# ChargerDeviceSchematic.net
KiCad netlist of a schematic drawn in Altium Designer
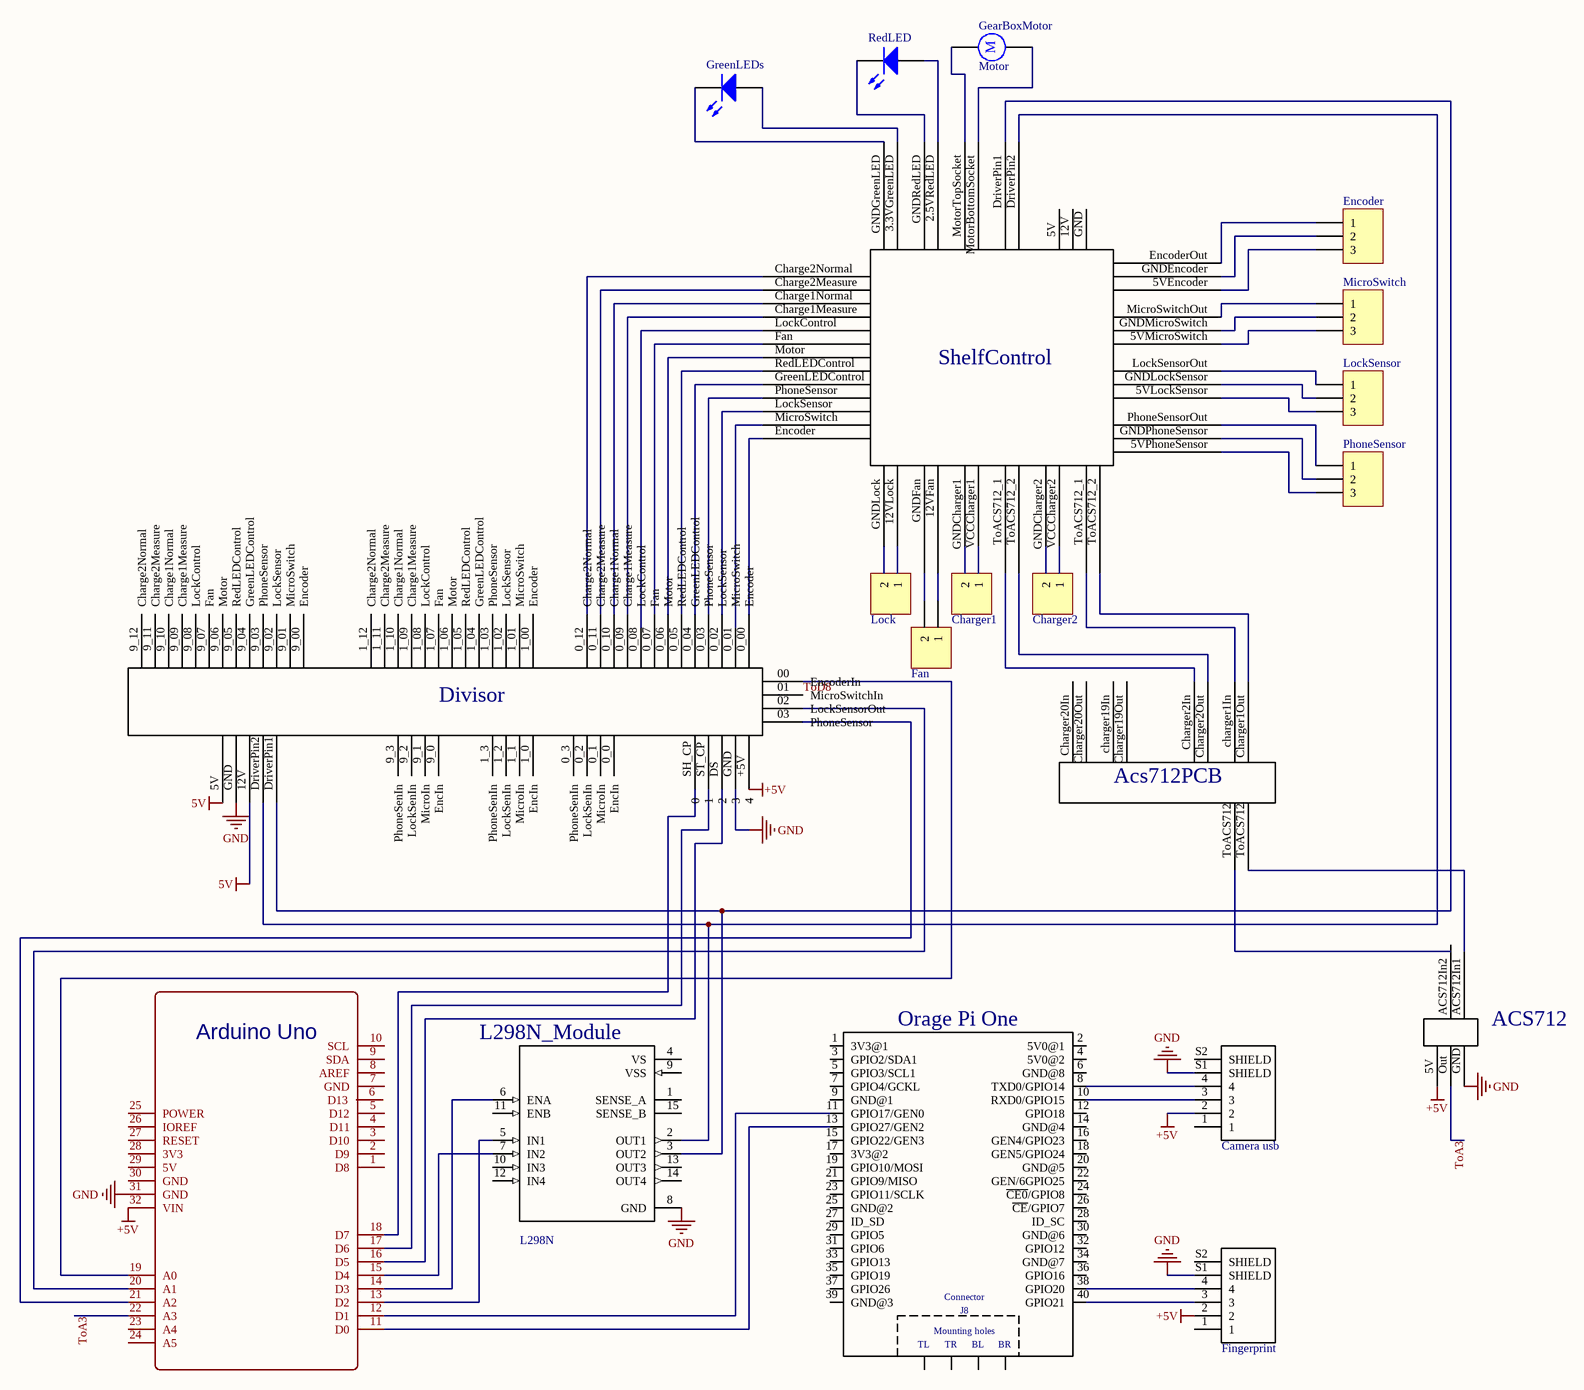
[diagram p0: ChargerDeviceSchematic.SchDoc]

(export (version "E")
  (design (tool "Eeschema 10.0.6"))
  (components
    (comp (ref "ACS712")
      (value "~")
      (footprint "CBB22")
      (description "Polypropylene film with epoxy Cap CBB22 105J400V")
      (fields (field (name "MANUFACTURER") "CHINA") (field (name "DESIGNER") "Abbas Basereh"))
      (libsource (lib "acs712") (part "Component_1"))
    )
    (comp (ref "Acs712PCB")
      (value "~")
      (footprint "CBB22")
      (description "Polypropylene film with epoxy Cap CBB22 105J400V")
      (fields (field (name "MANUFACTURER") "CHINA") (field (name "DESIGNER") "Abbas Basereh"))
      (libsource (lib "ACS712-connectBoard") (part "Component_1"))
    )
    (comp (ref "Arduino Uno")
      (value "~")
      (footprint "UNO_R3")
      (fields (field (name "BOM_MANUFACTURER PART") "?"))
      (libsource (lib "altium-import") (part "root_3_UNO_R3_"))
    )
    (comp (ref "Camera usb")
      (value "1-292303-1")
      (footprint "*TE_1-292303-1_1-292303-1(Primary)")
      (description "Conn USB 2.0 Type A RCP 4 POS Solder RA SMD 4 Terminal 1 Port Box/Tray")
      (fields (field (name "MF") "TE Connectivity"))
      (libsource (lib "1-292303-1") (part "1-292303-1"))
    )
    (comp (ref "Charger1")
      (value "~")
      (footprint "HDR1X2")
      (description "Header, 2-Pin")
      (fields (field (name "PUBLISHER") "Altium Limited"))
      (libsource (lib "Miscellaneous Connectors") (part "Header 2"))
    )
    (comp (ref "Charger2")
      (value "~")
      (footprint "HDR1X2")
      (description "Header, 2-Pin")
      (fields (field (name "PUBLISHER") "Altium Limited"))
      (libsource (lib "Miscellaneous Connectors") (part "Header 2"))
    )
    (comp (ref "Divisor")
      (value "~")
      (footprint "CBB22")
      (description "Polypropylene film with epoxy Cap CBB22 105J400V")
      (fields (field (name "MANUFACTURER") "CHINA") (field (name "DESIGNER") "Abbas Basereh"))
      (libsource (lib "divisor") (part "Component_1"))
    )
    (comp (ref "Encoder")
      (value "~")
      (footprint "HDR1X3")
      (description "Header, 3-Pin")
      (fields (field (name "PUBLISHER") "Altium Limited"))
      (libsource (lib "Miscellaneous Connectors") (part "Header 3"))
    )
    (comp (ref "Fan")
      (value "~")
      (footprint "HDR1X2")
      (description "Header, 2-Pin")
      (fields (field (name "PUBLISHER") "Altium Limited"))
      (libsource (lib "Miscellaneous Connectors") (part "Header 2"))
    )
    (comp (ref "Fingerprint")
      (value "1-292303-1")
      (footprint "*TE_1-292303-1_1-292303-1(Primary)")
      (description "Conn USB 2.0 Type A RCP 4 POS Solder RA SMD 4 Terminal 1 Port Box/Tray")
      (fields (field (name "MF") "TE Connectivity"))
      (libsource (lib "1-292303-1") (part "1-292303-1"))
    )
    (comp (ref "GearBoxMotor")
      (value "Motor")
      (footprint "RB5-10.5")
      (description "Motor, General Kind")
      (fields (field (name "PUBLISHER") "Altium Limited"))
      (libsource (lib "Miscellaneous Devices") (part "Motor"))
    )
    (comp (ref "GreenLEDs")
      (value "~")
      (footprint "3.2X1.6X1.1")
      (description "Typical RED, GREEN, YELLOW, AMBER GaAs LED")
      (fields (field (name "PUBLISHER") "Altium Limited"))
      (libsource (lib "Miscellaneous Devices") (part "LED2"))
    )
    (comp (ref "L298N_Module")
      (value "L298N")
      (footprint "*TO127P2020X500X2100-15")
      (description "Dual Full Bridge Motor Driver 15-Pin_15+Tab_ MULTIWATT V Tube")
      (fields (field (name "MF") "STMicroelectronics"))
      (libsource (lib "L298N") (part "L298N"))
    )
    (comp (ref "Lock")
      (value "~")
      (footprint "HDR1X2")
      (description "Header, 2-Pin")
      (fields (field (name "PUBLISHER") "Altium Limited"))
      (libsource (lib "Miscellaneous Connectors") (part "Header 2"))
    )
    (comp (ref "LockSensor")
      (value "~")
      (footprint "HDR1X3")
      (description "Header, 3-Pin")
      (fields (field (name "PUBLISHER") "Altium Limited"))
      (libsource (lib "Miscellaneous Connectors") (part "Header 3"))
    )
    (comp (ref "MicroSwitch")
      (value "~")
      (footprint "HDR1X3")
      (description "Header, 3-Pin")
      (fields (field (name "PUBLISHER") "Altium Limited"))
      (libsource (lib "Miscellaneous Connectors") (part "Header 3"))
    )
    (comp (ref "Orage Pi One")
      (value "~")
      (footprint "*RASPBERRY_PI_B+_RASPBERRY_PI_B+(Primary)")
      (description "Single Board Computer; 700Mhz; 512Mb RAM; 85.6x53.98x17mm; Raspberry Pi B+ Series")
      (fields (field (name "MF") "Raspberry Pi") (field (name "MP") "RASPBERRY PI B+"))
      (libsource (lib "RASPBERRY_PI_B_") (part "RASPBERRY_PI_B+"))
    )
    (comp (ref "PhoneSensor")
      (value "~")
      (footprint "HDR1X3")
      (description "Header, 3-Pin")
      (fields (field (name "PUBLISHER") "Altium Limited"))
      (libsource (lib "Miscellaneous Connectors") (part "Header 3"))
    )
    (comp (ref "RedLED")
      (value "~")
      (footprint "3.2X1.6X1.1")
      (description "Typical RED, GREEN, YELLOW, AMBER GaAs LED")
      (fields (field (name "PUBLISHER") "Altium Limited"))
      (libsource (lib "Miscellaneous Devices") (part "LED2"))
    )
    (comp (ref "ShelfControl")
      (value "~")
      (footprint "CBB22")
      (description "Polypropylene film with epoxy Cap CBB22 105J400V")
      (fields (field (name "MANUFACTURER") "CHINA") (field (name "DESIGNER") "Abbas Basereh"))
      (libsource (lib "shelfControl 5V") (part "Component_1"))
    )
  )
  (nets
    (net (code "1") (name "+5V") (class "Default")
      (node (ref "Arduino Uno") (pin "32") (pinfunction "VIN_32") (pintype "passive"))
      (node (ref "Camera usb") (pin "2") (pinfunction "2_2") (pintype "passive"))
      (node (ref "Fingerprint") (pin "2") (pinfunction "2_2") (pintype "passive"))
    )
    (net (code "2") (name "/ToA3") (class "Default")
      (node (ref "Arduino Uno") (pin "22") (pinfunction "A3_22") (pintype "passive"))
    )
    (net (code "5") (name "GND") (class "Default")
      (node (ref "Arduino Uno") (pin "31") (pinfunction "GND_31") (pintype "passive"))
      (node (ref "Camera usb") (pin "S1") (pinfunction "SHIELD_S1") (pintype "passive"))
      (node (ref "Fingerprint") (pin "S1") (pinfunction "SHIELD_S1") (pintype "passive"))
      (node (ref "L298N_Module") (pin "8") (pinfunction "GND_8") (pintype "power_in"))
    )
    (net (code "6") (name "Net-(Arduino Uno-D0)") (class "Default")
      (node (ref "Arduino Uno") (pin "11") (pinfunction "D0_11") (pintype "passive"))
      (node (ref "Orage Pi One") (pin "13") (pinfunction "GPIO27/GEN2_13") (pintype "bidirectional"))
    )
    (net (code "7") (name "Net-(Arduino Uno-D1)") (class "Default")
      (node (ref "Arduino Uno") (pin "12") (pinfunction "D1_12") (pintype "passive"))
      (node (ref "Orage Pi One") (pin "11") (pinfunction "GPIO17/GEN0_11") (pintype "bidirectional"))
    )
    (net (code "8") (name "Net-(Arduino Uno-D2)") (class "Default")
      (node (ref "Arduino Uno") (pin "13") (pinfunction "D2_13") (pintype "passive"))
      (node (ref "L298N_Module") (pin "5") (pinfunction "IN1_5") (pintype "input"))
    )
    (net (code "9") (name "Net-(Arduino Uno-D3)") (class "Default")
      (node (ref "Arduino Uno") (pin "14") (pinfunction "D3_14") (pintype "passive"))
      (node (ref "L298N_Module") (pin "6") (pinfunction "ENA_6") (pintype "input"))
    )
    (net (code "10") (name "Net-(Arduino Uno-D4)") (class "Default")
      (node (ref "Arduino Uno") (pin "15") (pinfunction "D4_15") (pintype "passive"))
      (node (ref "L298N_Module") (pin "7") (pinfunction "IN2_7") (pintype "input"))
    )
    (net (code "11") (name "Net-(Charger1-Pad1)") (class "Default")
      (node (ref "Charger1") (pin "1") (pinfunction "1_1") (pintype "passive"))
      (node (ref "ShelfControl") (pin "VCCCharger1") (pintype "passive"))
    )
    (net (code "12") (name "Net-(Charger1-Pad2)") (class "Default")
      (node (ref "Charger1") (pin "2") (pinfunction "2_2") (pintype "passive"))
      (node (ref "ShelfControl") (pin "GNDCharger1") (pintype "passive"))
    )
    (net (code "13") (name "Net-(Charger2-Pad1)") (class "Default")
      (node (ref "Charger2") (pin "1") (pinfunction "1_1") (pintype "passive"))
      (node (ref "ShelfControl") (pin "VCCCharger2") (pintype "passive"))
    )
    (net (code "14") (name "Net-(Charger2-Pad2)") (class "Default")
      (node (ref "Charger2") (pin "2") (pinfunction "2_2") (pintype "passive"))
      (node (ref "ShelfControl") (pin "GNDCharger2") (pintype "passive"))
    )
    (net (code "15") (name "Net-(Fan-Pad1)") (class "Default")
      (node (ref "Fan") (pin "1") (pinfunction "1_1") (pintype "passive"))
      (node (ref "ShelfControl") (pin "12VFan") (pintype "passive"))
    )
    (net (code "16") (name "Net-(Fan-Pad2)") (class "Default")
      (node (ref "Fan") (pin "2") (pinfunction "2_2") (pintype "passive"))
      (node (ref "ShelfControl") (pin "GNDFan") (pintype "passive"))
    )
    (net (code "17") (name "Net-(Lock-Pad1)") (class "Default")
      (node (ref "Lock") (pin "1") (pinfunction "1_1") (pintype "passive"))
      (node (ref "ShelfControl") (pin "12VLock") (pintype "passive"))
    )
    (net (code "18") (name "Net-(Lock-Pad2)") (class "Default")
      (node (ref "Lock") (pin "2") (pinfunction "2_2") (pintype "passive"))
      (node (ref "ShelfControl") (pin "GNDLock") (pintype "passive"))
    )
    (net (code "19") (name "Net-(Orage Pi One-GPIO20)") (class "Default")
      (node (ref "Fingerprint") (pin "4") (pinfunction "4_4") (pintype "passive"))
      (node (ref "Orage Pi One") (pin "38") (pinfunction "GPIO20_38") (pintype "bidirectional"))
    )
    (net (code "20") (name "Net-(Orage Pi One-GPIO21)") (class "Default")
      (node (ref "Fingerprint") (pin "3") (pinfunction "3_3") (pintype "passive"))
      (node (ref "Orage Pi One") (pin "40") (pinfunction "GPIO21_40") (pintype "bidirectional"))
    )
    (net (code "21") (name "Net-(Orage Pi One-RXD0{slash}GPIO15)") (class "Default")
      (node (ref "Camera usb") (pin "3") (pinfunction "3_3") (pintype "passive"))
      (node (ref "Orage Pi One") (pin "10") (pinfunction "RXD0/GPIO15_10") (pintype "bidirectional"))
    )
    (net (code "22") (name "Net-(Orage Pi One-TXD0{slash}GPIO14)") (class "Default")
      (node (ref "Camera usb") (pin "4") (pinfunction "4_4") (pintype "passive"))
      (node (ref "Orage Pi One") (pin "8") (pinfunction "TXD0/GPIO14_8") (pintype "bidirectional"))
    )
    (net (code "23") (name "unconnected-(ACS712-Pad5V)") (class "Default")
      (node (ref "ACS712") (pin "5V") (pintype "passive"))
    )
    (net (code "24") (name "unconnected-(ACS712-PadACS712In1)") (class "Default")
      (node (ref "ACS712") (pin "ACS712In1") (pintype "passive"))
    )
    (net (code "25") (name "unconnected-(ACS712-PadACS712In2)") (class "Default")
      (node (ref "ACS712") (pin "ACS712In2") (pintype "passive"))
    )
    (net (code "26") (name "unconnected-(ACS712-PadGND)") (class "Default")
      (node (ref "ACS712") (pin "GND") (pintype "passive"))
    )
    (net (code "27") (name "unconnected-(ACS712-PadOut)") (class "Default")
      (node (ref "ACS712") (pin "Out") (pintype "passive"))
    )
    (net (code "28") (name "unconnected-(Acs712PCB-PadCharger1Out)") (class "Default")
      (node (ref "Acs712PCB") (pin "Charger1Out") (pintype "passive"))
    )
    (net (code "29") (name "unconnected-(Acs712PCB-PadCharger2In)") (class "Default")
      (node (ref "Acs712PCB") (pin "Charger2In") (pintype "passive"))
    )
    (net (code "30") (name "unconnected-(Acs712PCB-PadCharger2Out)") (class "Default")
      (node (ref "Acs712PCB") (pin "Charger2Out") (pintype "passive"))
    )
    (net (code "31") (name "unconnected-(Acs712PCB-PadCharger19Out)") (class "Default")
      (node (ref "Acs712PCB") (pin "Charger19Out") (pintype "passive"))
    )
    (net (code "32") (name "unconnected-(Acs712PCB-PadCharger20In)") (class "Default")
      (node (ref "Acs712PCB") (pin "Charger20In") (pintype "passive"))
    )
    (net (code "33") (name "unconnected-(Acs712PCB-PadCharger20Out)") (class "Default")
      (node (ref "Acs712PCB") (pin "Charger20Out") (pintype "passive"))
    )
    (net (code "34") (name "unconnected-(Acs712PCB-PadToACS712)") (class "Default")
      (node (ref "Acs712PCB") (pin "ToACS712") (pintype "passive"))
    )
    (net (code "35") (name "unconnected-(Acs712PCB-PadToACS712)_1") (class "Default")
      (node (ref "Acs712PCB") (pin "ToACS712") (pintype "passive"))
    )
    (net (code "36") (name "unconnected-(Acs712PCB-Padcharger1In)") (class "Default")
      (node (ref "Acs712PCB") (pin "charger1In") (pintype "passive"))
    )
    (net (code "37") (name "unconnected-(Acs712PCB-Padcharger19In)") (class "Default")
      (node (ref "Acs712PCB") (pin "charger19In") (pintype "passive"))
    )
    (net (code "38") (name "unconnected-(Arduino Uno-3V3-Pad28)") (class "Default")
      (node (ref "Arduino Uno") (pin "28") (pinfunction "3V3_28") (pintype "passive"))
    )
    (net (code "39") (name "unconnected-(Arduino Uno-5V-Pad29)") (class "Default")
      (node (ref "Arduino Uno") (pin "29") (pinfunction "5V_29") (pintype "passive"))
    )
    (net (code "40") (name "unconnected-(Arduino Uno-A0-Pad19)") (class "Default")
      (node (ref "Arduino Uno") (pin "19") (pinfunction "A0_19") (pintype "passive"))
    )
    (net (code "41") (name "unconnected-(Arduino Uno-A1-Pad20)") (class "Default")
      (node (ref "Arduino Uno") (pin "20") (pinfunction "A1_20") (pintype "passive"))
    )
    (net (code "42") (name "unconnected-(Arduino Uno-A2-Pad21)") (class "Default")
      (node (ref "Arduino Uno") (pin "21") (pinfunction "A2_21") (pintype "passive"))
    )
    (net (code "43") (name "unconnected-(Arduino Uno-A4-Pad23)") (class "Default")
      (node (ref "Arduino Uno") (pin "23") (pinfunction "A4_23") (pintype "passive"))
    )
    (net (code "44") (name "unconnected-(Arduino Uno-A5-Pad24)") (class "Default")
      (node (ref "Arduino Uno") (pin "24") (pinfunction "A5_24") (pintype "passive"))
    )
    (net (code "45") (name "unconnected-(Arduino Uno-AREF-Pad8)") (class "Default")
      (node (ref "Arduino Uno") (pin "8") (pinfunction "AREF_8") (pintype "passive"))
    )
    (net (code "46") (name "unconnected-(Arduino Uno-D5-Pad16)") (class "Default")
      (node (ref "Arduino Uno") (pin "16") (pinfunction "D5_16") (pintype "passive"))
    )
    (net (code "47") (name "unconnected-(Arduino Uno-D6-Pad17)") (class "Default")
      (node (ref "Arduino Uno") (pin "17") (pinfunction "D6_17") (pintype "passive"))
    )
    (net (code "48") (name "unconnected-(Arduino Uno-D7-Pad18)") (class "Default")
      (node (ref "Arduino Uno") (pin "18") (pinfunction "D7_18") (pintype "passive"))
    )
    (net (code "49") (name "unconnected-(Arduino Uno-D8-Pad1)") (class "Default")
      (node (ref "Arduino Uno") (pin "1") (pinfunction "D8_1") (pintype "passive"))
    )
    (net (code "50") (name "unconnected-(Arduino Uno-D9-Pad2)") (class "Default")
      (node (ref "Arduino Uno") (pin "2") (pinfunction "D9_2") (pintype "passive"))
    )
    (net (code "51") (name "unconnected-(Arduino Uno-D10-Pad3)") (class "Default")
      (node (ref "Arduino Uno") (pin "3") (pinfunction "D10_3") (pintype "passive"))
    )
    (net (code "52") (name "unconnected-(Arduino Uno-D11-Pad4)") (class "Default")
      (node (ref "Arduino Uno") (pin "4") (pinfunction "D11_4") (pintype "passive"))
    )
    (net (code "53") (name "unconnected-(Arduino Uno-D12-Pad5)") (class "Default")
      (node (ref "Arduino Uno") (pin "5") (pinfunction "D12_5") (pintype "passive"))
    )
    (net (code "54") (name "unconnected-(Arduino Uno-D13-Pad6)") (class "Default")
      (node (ref "Arduino Uno") (pin "6") (pinfunction "D13_6") (pintype "passive"))
    )
    (net (code "55") (name "unconnected-(Arduino Uno-GND-Pad7)") (class "Default")
      (node (ref "Arduino Uno") (pin "7") (pinfunction "GND_7") (pintype "passive"))
    )
    (net (code "56") (name "unconnected-(Arduino Uno-GND-Pad30)") (class "Default")
      (node (ref "Arduino Uno") (pin "30") (pinfunction "GND_30") (pintype "passive"))
    )
    (net (code "57") (name "unconnected-(Arduino Uno-IOREF-Pad26)") (class "Default")
      (node (ref "Arduino Uno") (pin "26") (pinfunction "IOREF_26") (pintype "passive"))
    )
    (net (code "58") (name "unconnected-(Arduino Uno-POWER-Pad25)") (class "Default")
      (node (ref "Arduino Uno") (pin "25") (pinfunction "POWER_25") (pintype "passive"))
    )
    (net (code "59") (name "unconnected-(Arduino Uno-RESET-Pad27)") (class "Default")
      (node (ref "Arduino Uno") (pin "27") (pinfunction "RESET_27") (pintype "passive"))
    )
    (net (code "60") (name "unconnected-(Arduino Uno-SCL-Pad10)") (class "Default")
      (node (ref "Arduino Uno") (pin "10") (pinfunction "SCL_10") (pintype "passive"))
    )
    (net (code "61") (name "unconnected-(Arduino Uno-SDA-Pad9)") (class "Default")
      (node (ref "Arduino Uno") (pin "9") (pinfunction "SDA_9") (pintype "passive"))
    )
    (net (code "62") (name "unconnected-(Camera usb-Pad1)") (class "Default")
      (node (ref "Camera usb") (pin "1") (pinfunction "1_1") (pintype "passive"))
    )
    (net (code "63") (name "unconnected-(Camera usb-SHIELD-PadS2)") (class "Default")
      (node (ref "Camera usb") (pin "S2") (pinfunction "SHIELD_S2") (pintype "passive"))
    )
    (net (code "64") (name "unconnected-(Divisor-0-PadSH_CP)") (class "Default")
      (node (ref "Divisor") (pin "SH_CP") (pinfunction "0_SH_CP") (pintype "passive"))
    )
    (net (code "65") (name "unconnected-(Divisor-1-PadST_CP)") (class "Default")
      (node (ref "Divisor") (pin "ST_CP") (pinfunction "1_ST_CP") (pintype "passive"))
    )
    (net (code "66") (name "unconnected-(Divisor-2-PadDS)") (class "Default")
      (node (ref "Divisor") (pin "DS") (pinfunction "2_DS") (pintype "passive"))
    )
    (net (code "67") (name "unconnected-(Divisor-3-PadGND)") (class "Default")
      (node (ref "Divisor") (pin "GND") (pinfunction "3_GND") (pintype "passive"))
    )
    (net (code "68") (name "unconnected-(Divisor-4-Pad+5V)") (class "Default")
      (node (ref "Divisor") (pin "+5V") (pinfunction "4_+5V") (pintype "passive"))
    )
    (net (code "69") (name "unconnected-(Divisor-Charge1Measure-Pad0_09)") (class "Default")
      (node (ref "Divisor") (pin "0_09") (pinfunction "Charge1Measure_0_09") (pintype "passive"))
    )
    (net (code "70") (name "unconnected-(Divisor-Charge1Measure-Pad1_09)") (class "Default")
      (node (ref "Divisor") (pin "1_09") (pinfunction "Charge1Measure_1_09") (pintype "passive"))
    )
    (net (code "71") (name "unconnected-(Divisor-Charge1Measure-Pad9_09)") (class "Default")
      (node (ref "Divisor") (pin "9_09") (pinfunction "Charge1Measure_9_09") (pintype "passive"))
    )
    (net (code "72") (name "unconnected-(Divisor-Charge1Normal-Pad0_10)") (class "Default")
      (node (ref "Divisor") (pin "0_10") (pinfunction "Charge1Normal_0_10") (pintype "passive"))
    )
    (net (code "73") (name "unconnected-(Divisor-Charge1Normal-Pad1_10)") (class "Default")
      (node (ref "Divisor") (pin "1_10") (pinfunction "Charge1Normal_1_10") (pintype "passive"))
    )
    (net (code "74") (name "unconnected-(Divisor-Charge1Normal-Pad9_10)") (class "Default")
      (node (ref "Divisor") (pin "9_10") (pinfunction "Charge1Normal_9_10") (pintype "passive"))
    )
    (net (code "75") (name "unconnected-(Divisor-Charge2Measure-Pad0_11)") (class "Default")
      (node (ref "Divisor") (pin "0_11") (pinfunction "Charge2Measure_0_11") (pintype "passive"))
    )
    (net (code "76") (name "unconnected-(Divisor-Charge2Measure-Pad1_11)") (class "Default")
      (node (ref "Divisor") (pin "1_11") (pinfunction "Charge2Measure_1_11") (pintype "passive"))
    )
    (net (code "77") (name "unconnected-(Divisor-Charge2Measure-Pad9_11)") (class "Default")
      (node (ref "Divisor") (pin "9_11") (pinfunction "Charge2Measure_9_11") (pintype "passive"))
    )
    (net (code "78") (name "unconnected-(Divisor-Charge2Normal-Pad0_12)") (class "Default")
      (node (ref "Divisor") (pin "0_12") (pinfunction "Charge2Normal_0_12") (pintype "passive"))
    )
    (net (code "79") (name "unconnected-(Divisor-Charge2Normal-Pad1_12)") (class "Default")
      (node (ref "Divisor") (pin "1_12") (pinfunction "Charge2Normal_1_12") (pintype "passive"))
    )
    (net (code "80") (name "unconnected-(Divisor-Charge2Normal-Pad9_12)") (class "Default")
      (node (ref "Divisor") (pin "9_12") (pinfunction "Charge2Normal_9_12") (pintype "passive"))
    )
    (net (code "81") (name "unconnected-(Divisor-EncIn-Pad0_0)") (class "Default")
      (node (ref "Divisor") (pin "0_0") (pinfunction "EncIn_0_0") (pintype "passive"))
    )
    (net (code "82") (name "unconnected-(Divisor-EncIn-Pad1_0)") (class "Default")
      (node (ref "Divisor") (pin "1_0") (pinfunction "EncIn_1_0") (pintype "passive"))
    )
    (net (code "83") (name "unconnected-(Divisor-EncIn-Pad9_0)") (class "Default")
      (node (ref "Divisor") (pin "9_0") (pinfunction "EncIn_9_0") (pintype "passive"))
    )
    (net (code "84") (name "unconnected-(Divisor-Encoder-Pad0_00)") (class "Default")
      (node (ref "Divisor") (pin "0_00") (pinfunction "Encoder_0_00") (pintype "passive"))
    )
    (net (code "85") (name "unconnected-(Divisor-Encoder-Pad1_00)") (class "Default")
      (node (ref "Divisor") (pin "1_00") (pinfunction "Encoder_1_00") (pintype "passive"))
    )
    (net (code "86") (name "unconnected-(Divisor-Encoder-Pad9_00)") (class "Default")
      (node (ref "Divisor") (pin "9_00") (pinfunction "Encoder_9_00") (pintype "passive"))
    )
    (net (code "87") (name "unconnected-(Divisor-EncoderIn-Pad00)") (class "Default")
      (node (ref "Divisor") (pin "00") (pinfunction "EncoderIn_00") (pintype "passive"))
    )
    (net (code "88") (name "unconnected-(Divisor-Fan-Pad0_07)") (class "Default")
      (node (ref "Divisor") (pin "0_07") (pinfunction "Fan_0_07") (pintype "passive"))
    )
    (net (code "89") (name "unconnected-(Divisor-Fan-Pad1_07)") (class "Default")
      (node (ref "Divisor") (pin "1_07") (pinfunction "Fan_1_07") (pintype "passive"))
    )
    (net (code "90") (name "unconnected-(Divisor-Fan-Pad9_07)") (class "Default")
      (node (ref "Divisor") (pin "9_07") (pinfunction "Fan_9_07") (pintype "passive"))
    )
    (net (code "91") (name "unconnected-(Divisor-GreenLEDControl-Pad0_04)") (class "Default")
      (node (ref "Divisor") (pin "0_04") (pinfunction "GreenLEDControl_0_04") (pintype "passive"))
    )
    (net (code "92") (name "unconnected-(Divisor-GreenLEDControl-Pad1_04)") (class "Default")
      (node (ref "Divisor") (pin "1_04") (pinfunction "GreenLEDControl_1_04") (pintype "passive"))
    )
    (net (code "93") (name "unconnected-(Divisor-GreenLEDControl-Pad9_04)") (class "Default")
      (node (ref "Divisor") (pin "9_04") (pinfunction "GreenLEDControl_9_04") (pintype "passive"))
    )
    (net (code "94") (name "unconnected-(Divisor-LockControl-Pad0_08)") (class "Default")
      (node (ref "Divisor") (pin "0_08") (pinfunction "LockControl_0_08") (pintype "passive"))
    )
    (net (code "95") (name "unconnected-(Divisor-LockControl-Pad1_08)") (class "Default")
      (node (ref "Divisor") (pin "1_08") (pinfunction "LockControl_1_08") (pintype "passive"))
    )
    (net (code "96") (name "unconnected-(Divisor-LockControl-Pad9_08)") (class "Default")
      (node (ref "Divisor") (pin "9_08") (pinfunction "LockControl_9_08") (pintype "passive"))
    )
    (net (code "97") (name "unconnected-(Divisor-LockSenIn-Pad0_2)") (class "Default")
      (node (ref "Divisor") (pin "0_2") (pinfunction "LockSenIn_0_2") (pintype "passive"))
    )
    (net (code "98") (name "unconnected-(Divisor-LockSenIn-Pad1_2)") (class "Default")
      (node (ref "Divisor") (pin "1_2") (pinfunction "LockSenIn_1_2") (pintype "passive"))
    )
    (net (code "99") (name "unconnected-(Divisor-LockSenIn-Pad9_2)") (class "Default")
      (node (ref "Divisor") (pin "9_2") (pinfunction "LockSenIn_9_2") (pintype "passive"))
    )
    (net (code "100") (name "unconnected-(Divisor-LockSensor-Pad0_02)") (class "Default")
      (node (ref "Divisor") (pin "0_02") (pinfunction "LockSensor_0_02") (pintype "passive"))
    )
    (net (code "101") (name "unconnected-(Divisor-LockSensor-Pad1_02)") (class "Default")
      (node (ref "Divisor") (pin "1_02") (pinfunction "LockSensor_1_02") (pintype "passive"))
    )
    (net (code "102") (name "unconnected-(Divisor-LockSensor-Pad9_02)") (class "Default")
      (node (ref "Divisor") (pin "9_02") (pinfunction "LockSensor_9_02") (pintype "passive"))
    )
    (net (code "103") (name "unconnected-(Divisor-LockSensorOut-Pad02)") (class "Default")
      (node (ref "Divisor") (pin "02") (pinfunction "LockSensorOut_02") (pintype "passive"))
    )
    (net (code "104") (name "unconnected-(Divisor-MicroIn-Pad0_1)") (class "Default")
      (node (ref "Divisor") (pin "0_1") (pinfunction "MicroIn_0_1") (pintype "passive"))
    )
    (net (code "105") (name "unconnected-(Divisor-MicroIn-Pad1_1)") (class "Default")
      (node (ref "Divisor") (pin "1_1") (pinfunction "MicroIn_1_1") (pintype "passive"))
    )
    (net (code "106") (name "unconnected-(Divisor-MicroIn-Pad9_1)") (class "Default")
      (node (ref "Divisor") (pin "9_1") (pinfunction "MicroIn_9_1") (pintype "passive"))
    )
    (net (code "107") (name "unconnected-(Divisor-MicroSwitch-Pad0_01)") (class "Default")
      (node (ref "Divisor") (pin "0_01") (pinfunction "MicroSwitch_0_01") (pintype "passive"))
    )
    (net (code "108") (name "unconnected-(Divisor-MicroSwitch-Pad1_01)") (class "Default")
      (node (ref "Divisor") (pin "1_01") (pinfunction "MicroSwitch_1_01") (pintype "passive"))
    )
    (net (code "109") (name "unconnected-(Divisor-MicroSwitch-Pad9_01)") (class "Default")
      (node (ref "Divisor") (pin "9_01") (pinfunction "MicroSwitch_9_01") (pintype "passive"))
    )
    (net (code "110") (name "unconnected-(Divisor-MicroSwitchIn-Pad01)") (class "Default")
      (node (ref "Divisor") (pin "01") (pinfunction "MicroSwitchIn_01") (pintype "passive"))
    )
    (net (code "111") (name "unconnected-(Divisor-Motor-Pad0_06)") (class "Default")
      (node (ref "Divisor") (pin "0_06") (pinfunction "Motor_0_06") (pintype "passive"))
    )
    (net (code "112") (name "unconnected-(Divisor-Motor-Pad1_06)") (class "Default")
      (node (ref "Divisor") (pin "1_06") (pinfunction "Motor_1_06") (pintype "passive"))
    )
    (net (code "113") (name "unconnected-(Divisor-Motor-Pad9_06)") (class "Default")
      (node (ref "Divisor") (pin "9_06") (pinfunction "Motor_9_06") (pintype "passive"))
    )
    (net (code "114") (name "unconnected-(Divisor-Pad5V)") (class "Default")
      (node (ref "Divisor") (pin "5V") (pintype "passive"))
    )
    (net (code "115") (name "unconnected-(Divisor-Pad12V)") (class "Default")
      (node (ref "Divisor") (pin "12V") (pintype "passive"))
    )
    (net (code "116") (name "unconnected-(Divisor-PadDriverPin1)") (class "Default")
      (node (ref "Divisor") (pin "DriverPin1") (pintype "passive"))
    )
    (net (code "117") (name "unconnected-(Divisor-PadDriverPin2)") (class "Default")
      (node (ref "Divisor") (pin "DriverPin2") (pintype "passive"))
    )
    (net (code "118") (name "unconnected-(Divisor-PadGND)") (class "Default")
      (node (ref "Divisor") (pin "GND") (pintype "passive"))
    )
    (net (code "119") (name "unconnected-(Divisor-PhoneSenIn-Pad0_3)") (class "Default")
      (node (ref "Divisor") (pin "0_3") (pinfunction "PhoneSenIn_0_3") (pintype "passive"))
    )
    (net (code "120") (name "unconnected-(Divisor-PhoneSenIn-Pad1_3)") (class "Default")
      (node (ref "Divisor") (pin "1_3") (pinfunction "PhoneSenIn_1_3") (pintype "passive"))
    )
    (net (code "121") (name "unconnected-(Divisor-PhoneSenIn-Pad9_3)") (class "Default")
      (node (ref "Divisor") (pin "9_3") (pinfunction "PhoneSenIn_9_3") (pintype "passive"))
    )
    (net (code "122") (name "unconnected-(Divisor-PhoneSensor-Pad0_03)") (class "Default")
      (node (ref "Divisor") (pin "0_03") (pinfunction "PhoneSensor_0_03") (pintype "passive"))
    )
    (net (code "123") (name "unconnected-(Divisor-PhoneSensor-Pad1_03)") (class "Default")
      (node (ref "Divisor") (pin "1_03") (pinfunction "PhoneSensor_1_03") (pintype "passive"))
    )
    (net (code "124") (name "unconnected-(Divisor-PhoneSensor-Pad03)") (class "Default")
      (node (ref "Divisor") (pin "03") (pinfunction "PhoneSensor_03") (pintype "passive"))
    )
    (net (code "125") (name "unconnected-(Divisor-PhoneSensor-Pad9_03)") (class "Default")
      (node (ref "Divisor") (pin "9_03") (pinfunction "PhoneSensor_9_03") (pintype "passive"))
    )
    (net (code "126") (name "unconnected-(Divisor-RedLEDControl-Pad0_05)") (class "Default")
      (node (ref "Divisor") (pin "0_05") (pinfunction "RedLEDControl_0_05") (pintype "passive"))
    )
    (net (code "127") (name "unconnected-(Divisor-RedLEDControl-Pad1_05)") (class "Default")
      (node (ref "Divisor") (pin "1_05") (pinfunction "RedLEDControl_1_05") (pintype "passive"))
    )
    (net (code "128") (name "unconnected-(Divisor-RedLEDControl-Pad9_05)") (class "Default")
      (node (ref "Divisor") (pin "9_05") (pinfunction "RedLEDControl_9_05") (pintype "passive"))
    )
    (net (code "129") (name "unconnected-(Encoder-Pad1)") (class "Default")
      (node (ref "Encoder") (pin "1") (pinfunction "1_1") (pintype "passive"))
    )
    (net (code "130") (name "unconnected-(Encoder-Pad2)") (class "Default")
      (node (ref "Encoder") (pin "2") (pinfunction "2_2") (pintype "passive"))
    )
    (net (code "131") (name "unconnected-(Encoder-Pad3)") (class "Default")
      (node (ref "Encoder") (pin "3") (pinfunction "3_3") (pintype "passive"))
    )
    (net (code "132") (name "unconnected-(Fingerprint-Pad1)") (class "Default")
      (node (ref "Fingerprint") (pin "1") (pinfunction "1_1") (pintype "passive"))
    )
    (net (code "133") (name "unconnected-(Fingerprint-SHIELD-PadS2)") (class "Default")
      (node (ref "Fingerprint") (pin "S2") (pinfunction "SHIELD_S2") (pintype "passive"))
    )
    (net (code "134") (name "unconnected-(GearBoxMotor-Pad1)") (class "Default")
      (node (ref "GearBoxMotor") (pin "1") (pinfunction "1_1") (pintype "passive"))
    )
    (net (code "135") (name "unconnected-(GearBoxMotor-Pad2)") (class "Default")
      (node (ref "GearBoxMotor") (pin "2") (pinfunction "2_2") (pintype "passive"))
    )
    (net (code "136") (name "unconnected-(GreenLEDs-A-Pad1)") (class "Default")
      (node (ref "GreenLEDs") (pin "1") (pinfunction "A_1") (pintype "passive"))
    )
    (net (code "137") (name "unconnected-(GreenLEDs-K-Pad2)") (class "Default")
      (node (ref "GreenLEDs") (pin "2") (pinfunction "K_2") (pintype "passive"))
    )
    (net (code "138") (name "unconnected-(L298N_Module-ENB-Pad11)") (class "Default")
      (node (ref "L298N_Module") (pin "11") (pinfunction "ENB_11") (pintype "input"))
    )
    (net (code "139") (name "unconnected-(L298N_Module-IN3-Pad10)") (class "Default")
      (node (ref "L298N_Module") (pin "10") (pinfunction "IN3_10") (pintype "input"))
    )
    (net (code "140") (name "unconnected-(L298N_Module-IN4-Pad12)") (class "Default")
      (node (ref "L298N_Module") (pin "12") (pinfunction "IN4_12") (pintype "input"))
    )
    (net (code "141") (name "unconnected-(L298N_Module-OUT1-Pad2)") (class "Default")
      (node (ref "L298N_Module") (pin "2") (pinfunction "OUT1_2") (pintype "output"))
    )
    (net (code "142") (name "unconnected-(L298N_Module-OUT2-Pad3)") (class "Default")
      (node (ref "L298N_Module") (pin "3") (pinfunction "OUT2_3") (pintype "output"))
    )
    (net (code "143") (name "unconnected-(L298N_Module-OUT3-Pad13)") (class "Default")
      (node (ref "L298N_Module") (pin "13") (pinfunction "OUT3_13") (pintype "output"))
    )
    (net (code "144") (name "unconnected-(L298N_Module-OUT4-Pad14)") (class "Default")
      (node (ref "L298N_Module") (pin "14") (pinfunction "OUT4_14") (pintype "output"))
    )
    (net (code "145") (name "unconnected-(L298N_Module-SENSE_A-Pad1)") (class "Default")
      (node (ref "L298N_Module") (pin "1") (pinfunction "SENSE_A_1") (pintype "passive"))
    )
    (net (code "146") (name "unconnected-(L298N_Module-SENSE_B-Pad15)") (class "Default")
      (node (ref "L298N_Module") (pin "15") (pinfunction "SENSE_B_15") (pintype "passive"))
    )
    (net (code "147") (name "unconnected-(L298N_Module-VS-Pad4)") (class "Default")
      (node (ref "L298N_Module") (pin "4") (pinfunction "VS_4") (pintype "power_in"))
    )
    (net (code "148") (name "unconnected-(L298N_Module-VSS-Pad9)") (class "Default")
      (node (ref "L298N_Module") (pin "9") (pinfunction "VSS_9") (pintype "input"))
    )
    (net (code "149") (name "unconnected-(LockSensor-Pad1)") (class "Default")
      (node (ref "LockSensor") (pin "1") (pinfunction "1_1") (pintype "passive"))
    )
    (net (code "150") (name "unconnected-(LockSensor-Pad2)") (class "Default")
      (node (ref "LockSensor") (pin "2") (pinfunction "2_2") (pintype "passive"))
    )
    (net (code "151") (name "unconnected-(LockSensor-Pad3)") (class "Default")
      (node (ref "LockSensor") (pin "3") (pinfunction "3_3") (pintype "passive"))
    )
    (net (code "152") (name "unconnected-(MicroSwitch-Pad1)") (class "Default")
      (node (ref "MicroSwitch") (pin "1") (pinfunction "1_1") (pintype "passive"))
    )
    (net (code "153") (name "unconnected-(MicroSwitch-Pad2)") (class "Default")
      (node (ref "MicroSwitch") (pin "2") (pinfunction "2_2") (pintype "passive"))
    )
    (net (code "154") (name "unconnected-(MicroSwitch-Pad3)") (class "Default")
      (node (ref "MicroSwitch") (pin "3") (pinfunction "3_3") (pintype "passive"))
    )
    (net (code "155") (name "unconnected-(Orage Pi One-3V3@1-Pad1)") (class "Default")
      (node (ref "Orage Pi One") (pin "1") (pinfunction "3V3@1_1") (pintype "power_in"))
    )
    (net (code "156") (name "unconnected-(Orage Pi One-3V3@2-Pad17)") (class "Default")
      (node (ref "Orage Pi One") (pin "17") (pinfunction "3V3@2_17") (pintype "power_in"))
    )
    (net (code "157") (name "unconnected-(Orage Pi One-5V0@1-Pad2)") (class "Default")
      (node (ref "Orage Pi One") (pin "2") (pinfunction "5V0@1_2") (pintype "power_in"))
    )
    (net (code "158") (name "unconnected-(Orage Pi One-5V0@2-Pad4)") (class "Default")
      (node (ref "Orage Pi One") (pin "4") (pinfunction "5V0@2_4") (pintype "power_in"))
    )
    (net (code "159") (name "unconnected-(Orage Pi One-BL-PadPE_BL)") (class "Default")
      (node (ref "Orage Pi One") (pin "PE_BL") (pinfunction "BL_PE_BL") (pintype "bidirectional"))
    )
    (net (code "160") (name "unconnected-(Orage Pi One-BR-PadPE_BR)") (class "Default")
      (node (ref "Orage Pi One") (pin "PE_BR") (pinfunction "BR_PE_BR") (pintype "bidirectional"))
    )
    (net (code "161") (name "unconnected-(Orage Pi One-GEN4{slash}GPIO23-Pad16)") (class "Default")
      (node (ref "Orage Pi One") (pin "16") (pinfunction "GEN4/GPIO23_16") (pintype "bidirectional"))
    )
    (net (code "162") (name "unconnected-(Orage Pi One-GEN5{slash}GPIO24-Pad18)") (class "Default")
      (node (ref "Orage Pi One") (pin "18") (pinfunction "GEN5/GPIO24_18") (pintype "bidirectional"))
    )
    (net (code "163") (name "unconnected-(Orage Pi One-GEN{slash}6GPIO25-Pad22)") (class "Default")
      (node (ref "Orage Pi One") (pin "22") (pinfunction "GEN/6GPIO25_22") (pintype "bidirectional"))
    )
    (net (code "164") (name "unconnected-(Orage Pi One-GND@1-Pad9)") (class "Default")
      (node (ref "Orage Pi One") (pin "9") (pinfunction "GND@1_9") (pintype "power_in"))
    )
    (net (code "165") (name "unconnected-(Orage Pi One-GND@2-Pad25)") (class "Default")
      (node (ref "Orage Pi One") (pin "25") (pinfunction "GND@2_25") (pintype "power_in"))
    )
    (net (code "166") (name "unconnected-(Orage Pi One-GND@3-Pad39)") (class "Default")
      (node (ref "Orage Pi One") (pin "39") (pinfunction "GND@3_39") (pintype "power_in"))
    )
    (net (code "167") (name "unconnected-(Orage Pi One-GND@4-Pad14)") (class "Default")
      (node (ref "Orage Pi One") (pin "14") (pinfunction "GND@4_14") (pintype "power_in"))
    )
    (net (code "168") (name "unconnected-(Orage Pi One-GND@5-Pad20)") (class "Default")
      (node (ref "Orage Pi One") (pin "20") (pinfunction "GND@5_20") (pintype "power_in"))
    )
    (net (code "169") (name "unconnected-(Orage Pi One-GND@6-Pad30)") (class "Default")
      (node (ref "Orage Pi One") (pin "30") (pinfunction "GND@6_30") (pintype "power_in"))
    )
    (net (code "170") (name "unconnected-(Orage Pi One-GND@7-Pad34)") (class "Default")
      (node (ref "Orage Pi One") (pin "34") (pinfunction "GND@7_34") (pintype "power_in"))
    )
    (net (code "171") (name "unconnected-(Orage Pi One-GND@8-Pad6)") (class "Default")
      (node (ref "Orage Pi One") (pin "6") (pinfunction "GND@8_6") (pintype "power_in"))
    )
    (net (code "172") (name "unconnected-(Orage Pi One-GPIO2{slash}SDA1-Pad3)") (class "Default")
      (node (ref "Orage Pi One") (pin "3") (pinfunction "GPIO2/SDA1_3") (pintype "bidirectional"))
    )
    (net (code "173") (name "unconnected-(Orage Pi One-GPIO3{slash}SCL1-Pad5)") (class "Default")
      (node (ref "Orage Pi One") (pin "5") (pinfunction "GPIO3/SCL1_5") (pintype "bidirectional"))
    )
    (net (code "174") (name "unconnected-(Orage Pi One-GPIO4{slash}GCKL-Pad7)") (class "Default")
      (node (ref "Orage Pi One") (pin "7") (pinfunction "GPIO4/GCKL_7") (pintype "bidirectional"))
    )
    (net (code "175") (name "unconnected-(Orage Pi One-GPIO5-Pad29)") (class "Default")
      (node (ref "Orage Pi One") (pin "29") (pinfunction "GPIO5_29") (pintype "bidirectional"))
    )
    (net (code "176") (name "unconnected-(Orage Pi One-GPIO6-Pad31)") (class "Default")
      (node (ref "Orage Pi One") (pin "31") (pinfunction "GPIO6_31") (pintype "bidirectional"))
    )
    (net (code "177") (name "unconnected-(Orage Pi One-GPIO9{slash}MISO-Pad21)") (class "Default")
      (node (ref "Orage Pi One") (pin "21") (pinfunction "GPIO9/MISO_21") (pintype "bidirectional"))
    )
    (net (code "178") (name "unconnected-(Orage Pi One-GPIO10{slash}MOSI-Pad19)") (class "Default")
      (node (ref "Orage Pi One") (pin "19") (pinfunction "GPIO10/MOSI_19") (pintype "bidirectional"))
    )
    (net (code "179") (name "unconnected-(Orage Pi One-GPIO11{slash}SCLK-Pad23)") (class "Default")
      (node (ref "Orage Pi One") (pin "23") (pinfunction "GPIO11/SCLK_23") (pintype "bidirectional"))
    )
    (net (code "180") (name "unconnected-(Orage Pi One-GPIO12-Pad32)") (class "Default")
      (node (ref "Orage Pi One") (pin "32") (pinfunction "GPIO12_32") (pintype "bidirectional"))
    )
    (net (code "181") (name "unconnected-(Orage Pi One-GPIO13-Pad33)") (class "Default")
      (node (ref "Orage Pi One") (pin "33") (pinfunction "GPIO13_33") (pintype "bidirectional"))
    )
    (net (code "182") (name "unconnected-(Orage Pi One-GPIO16-Pad36)") (class "Default")
      (node (ref "Orage Pi One") (pin "36") (pinfunction "GPIO16_36") (pintype "bidirectional"))
    )
    (net (code "183") (name "unconnected-(Orage Pi One-GPIO18-Pad12)") (class "Default")
      (node (ref "Orage Pi One") (pin "12") (pinfunction "GPIO18_12") (pintype "bidirectional"))
    )
    (net (code "184") (name "unconnected-(Orage Pi One-GPIO19-Pad35)") (class "Default")
      (node (ref "Orage Pi One") (pin "35") (pinfunction "GPIO19_35") (pintype "bidirectional"))
    )
    (net (code "185") (name "unconnected-(Orage Pi One-GPIO22{slash}GEN3-Pad15)") (class "Default")
      (node (ref "Orage Pi One") (pin "15") (pinfunction "GPIO22/GEN3_15") (pintype "bidirectional"))
    )
    (net (code "186") (name "unconnected-(Orage Pi One-GPIO26-Pad37)") (class "Default")
      (node (ref "Orage Pi One") (pin "37") (pinfunction "GPIO26_37") (pintype "bidirectional"))
    )
    (net (code "187") (name "unconnected-(Orage Pi One-ID_SC-Pad28)") (class "Default")
      (node (ref "Orage Pi One") (pin "28") (pinfunction "ID_SC_28") (pintype "bidirectional"))
    )
    (net (code "188") (name "unconnected-(Orage Pi One-ID_SD-Pad27)") (class "Default")
      (node (ref "Orage Pi One") (pin "27") (pinfunction "ID_SD_27") (pintype "bidirectional"))
    )
    (net (code "189") (name "unconnected-(Orage Pi One-TL-PadPE_TL)") (class "Default")
      (node (ref "Orage Pi One") (pin "PE_TL") (pinfunction "TL_PE_TL") (pintype "bidirectional"))
    )
    (net (code "190") (name "unconnected-(Orage Pi One-TR-PadPE_TR)") (class "Default")
      (node (ref "Orage Pi One") (pin "PE_TR") (pinfunction "TR_PE_TR") (pintype "bidirectional"))
    )
    (net (code "191") (name "unconnected-(Orage Pi One-~{CE0}{slash}GPIO8-Pad24)") (class "Default")
      (node (ref "Orage Pi One") (pin "24") (pinfunction "~{CE0}/GPIO8_24") (pintype "bidirectional"))
    )
    (net (code "192") (name "unconnected-(Orage Pi One-~{CE}{slash}GPIO7-Pad26)") (class "Default")
      (node (ref "Orage Pi One") (pin "26") (pinfunction "~{CE}/GPIO7_26") (pintype "bidirectional"))
    )
    (net (code "193") (name "unconnected-(PhoneSensor-Pad1)") (class "Default")
      (node (ref "PhoneSensor") (pin "1") (pinfunction "1_1") (pintype "passive"))
    )
    (net (code "194") (name "unconnected-(PhoneSensor-Pad2)") (class "Default")
      (node (ref "PhoneSensor") (pin "2") (pinfunction "2_2") (pintype "passive"))
    )
    (net (code "195") (name "unconnected-(PhoneSensor-Pad3)") (class "Default")
      (node (ref "PhoneSensor") (pin "3") (pinfunction "3_3") (pintype "passive"))
    )
    (net (code "196") (name "unconnected-(RedLED-A-Pad1)") (class "Default")
      (node (ref "RedLED") (pin "1") (pinfunction "A_1") (pintype "passive"))
    )
    (net (code "197") (name "unconnected-(RedLED-K-Pad2)") (class "Default")
      (node (ref "RedLED") (pin "2") (pinfunction "K_2") (pintype "passive"))
    )
    (net (code "198") (name "unconnected-(ShelfControl-Pad2.5VRedLED)") (class "Default")
      (node (ref "ShelfControl") (pin "2.5VRedLED") (pintype "passive"))
    )
    (net (code "199") (name "unconnected-(ShelfControl-Pad3.3VGreenLED)") (class "Default")
      (node (ref "ShelfControl") (pin "3.3VGreenLED") (pintype "passive"))
    )
    (net (code "200") (name "unconnected-(ShelfControl-Pad5V)") (class "Default")
      (node (ref "ShelfControl") (pin "5V") (pintype "passive"))
    )
    (net (code "201") (name "unconnected-(ShelfControl-Pad5VEncoder)") (class "Default")
      (node (ref "ShelfControl") (pin "5VEncoder") (pintype "passive"))
    )
    (net (code "202") (name "unconnected-(ShelfControl-Pad5VLockSensor)") (class "Default")
      (node (ref "ShelfControl") (pin "5VLockSensor") (pintype "passive"))
    )
    (net (code "203") (name "unconnected-(ShelfControl-Pad5VMicroSwitch)") (class "Default")
      (node (ref "ShelfControl") (pin "5VMicroSwitch") (pintype "passive"))
    )
    (net (code "204") (name "unconnected-(ShelfControl-Pad5VPhoneSensor)") (class "Default")
      (node (ref "ShelfControl") (pin "5VPhoneSensor") (pintype "passive"))
    )
    (net (code "205") (name "unconnected-(ShelfControl-Pad12V)") (class "Default")
      (node (ref "ShelfControl") (pin "12V") (pintype "passive"))
    )
    (net (code "206") (name "unconnected-(ShelfControl-PadCharge1Measure)") (class "Default")
      (node (ref "ShelfControl") (pin "Charge1Measure") (pintype "passive"))
    )
    (net (code "207") (name "unconnected-(ShelfControl-PadCharge1Normal)") (class "Default")
      (node (ref "ShelfControl") (pin "Charge1Normal") (pintype "passive"))
    )
    (net (code "208") (name "unconnected-(ShelfControl-PadCharge2Measure)") (class "Default")
      (node (ref "ShelfControl") (pin "Charge2Measure") (pintype "passive"))
    )
    (net (code "209") (name "unconnected-(ShelfControl-PadCharge2Normal)") (class "Default")
      (node (ref "ShelfControl") (pin "Charge2Normal") (pintype "passive"))
    )
    (net (code "210") (name "unconnected-(ShelfControl-PadDriverPin1)") (class "Default")
      (node (ref "ShelfControl") (pin "DriverPin1") (pintype "passive"))
    )
    (net (code "211") (name "unconnected-(ShelfControl-PadDriverPin2)") (class "Default")
      (node (ref "ShelfControl") (pin "DriverPin2") (pintype "passive"))
    )
    (net (code "212") (name "unconnected-(ShelfControl-PadEncoder)") (class "Default")
      (node (ref "ShelfControl") (pin "Encoder") (pintype "passive"))
    )
    (net (code "213") (name "unconnected-(ShelfControl-PadEncoderOut)") (class "Default")
      (node (ref "ShelfControl") (pin "EncoderOut") (pintype "passive"))
    )
    (net (code "214") (name "unconnected-(ShelfControl-PadFan)") (class "Default")
      (node (ref "ShelfControl") (pin "Fan") (pintype "passive"))
    )
    (net (code "215") (name "unconnected-(ShelfControl-PadGND)") (class "Default")
      (node (ref "ShelfControl") (pin "GND") (pintype "passive"))
    )
    (net (code "216") (name "unconnected-(ShelfControl-PadGNDEncoder)") (class "Default")
      (node (ref "ShelfControl") (pin "GNDEncoder") (pintype "passive"))
    )
    (net (code "217") (name "unconnected-(ShelfControl-PadGNDGreenLED)") (class "Default")
      (node (ref "ShelfControl") (pin "GNDGreenLED") (pintype "passive"))
    )
    (net (code "218") (name "unconnected-(ShelfControl-PadGNDLockSensor)") (class "Default")
      (node (ref "ShelfControl") (pin "GNDLockSensor") (pintype "passive"))
    )
    (net (code "219") (name "unconnected-(ShelfControl-PadGNDMicroSwitch)") (class "Default")
      (node (ref "ShelfControl") (pin "GNDMicroSwitch") (pintype "passive"))
    )
    (net (code "220") (name "unconnected-(ShelfControl-PadGNDPhoneSensor)") (class "Default")
      (node (ref "ShelfControl") (pin "GNDPhoneSensor") (pintype "passive"))
    )
    (net (code "221") (name "unconnected-(ShelfControl-PadGNDRedLED)") (class "Default")
      (node (ref "ShelfControl") (pin "GNDRedLED") (pintype "passive"))
    )
    (net (code "222") (name "unconnected-(ShelfControl-PadGreenLEDControl)") (class "Default")
      (node (ref "ShelfControl") (pin "GreenLEDControl") (pintype "passive"))
    )
    (net (code "223") (name "unconnected-(ShelfControl-PadLockControl)") (class "Default")
      (node (ref "ShelfControl") (pin "LockControl") (pintype "passive"))
    )
    (net (code "224") (name "unconnected-(ShelfControl-PadLockSensor)") (class "Default")
      (node (ref "ShelfControl") (pin "LockSensor") (pintype "passive"))
    )
    (net (code "225") (name "unconnected-(ShelfControl-PadLockSensorOut)") (class "Default")
      (node (ref "ShelfControl") (pin "LockSensorOut") (pintype "passive"))
    )
    (net (code "226") (name "unconnected-(ShelfControl-PadMicroSwitch)") (class "Default")
      (node (ref "ShelfControl") (pin "MicroSwitch") (pintype "passive"))
    )
    (net (code "227") (name "unconnected-(ShelfControl-PadMicroSwitchOut)") (class "Default")
      (node (ref "ShelfControl") (pin "MicroSwitchOut") (pintype "passive"))
    )
    (net (code "228") (name "unconnected-(ShelfControl-PadMotor)") (class "Default")
      (node (ref "ShelfControl") (pin "Motor") (pintype "passive"))
    )
    (net (code "229") (name "unconnected-(ShelfControl-PadMotorBottomSocket)") (class "Default")
      (node (ref "ShelfControl") (pin "MotorBottomSocket") (pintype "passive"))
    )
    (net (code "230") (name "unconnected-(ShelfControl-PadMotorTopSocket)") (class "Default")
      (node (ref "ShelfControl") (pin "MotorTopSocket") (pintype "passive"))
    )
    (net (code "231") (name "unconnected-(ShelfControl-PadPhoneSensor)") (class "Default")
      (node (ref "ShelfControl") (pin "PhoneSensor") (pintype "passive"))
    )
    (net (code "232") (name "unconnected-(ShelfControl-PadPhoneSensorOut)") (class "Default")
      (node (ref "ShelfControl") (pin "PhoneSensorOut") (pintype "passive"))
    )
    (net (code "233") (name "unconnected-(ShelfControl-PadRedLEDControl)") (class "Default")
      (node (ref "ShelfControl") (pin "RedLEDControl") (pintype "passive"))
    )
    (net (code "234") (name "unconnected-(ShelfControl-PadToACS712_1)") (class "Default")
      (node (ref "ShelfControl") (pin "ToACS712_1") (pintype "passive"))
    )
    (net (code "235") (name "unconnected-(ShelfControl-PadToACS712_1)_1") (class "Default")
      (node (ref "ShelfControl") (pin "ToACS712_1") (pintype "passive"))
    )
    (net (code "236") (name "unconnected-(ShelfControl-PadToACS712_2)") (class "Default")
      (node (ref "ShelfControl") (pin "ToACS712_2") (pintype "passive"))
    )
    (net (code "237") (name "unconnected-(ShelfControl-PadToACS712_2)_1") (class "Default")
      (node (ref "ShelfControl") (pin "ToACS712_2") (pintype "passive"))
    )
  )
)
